# 08_JTAG_DEBUG.net
KiCad netlist of a schematic drawn in Altium Designer
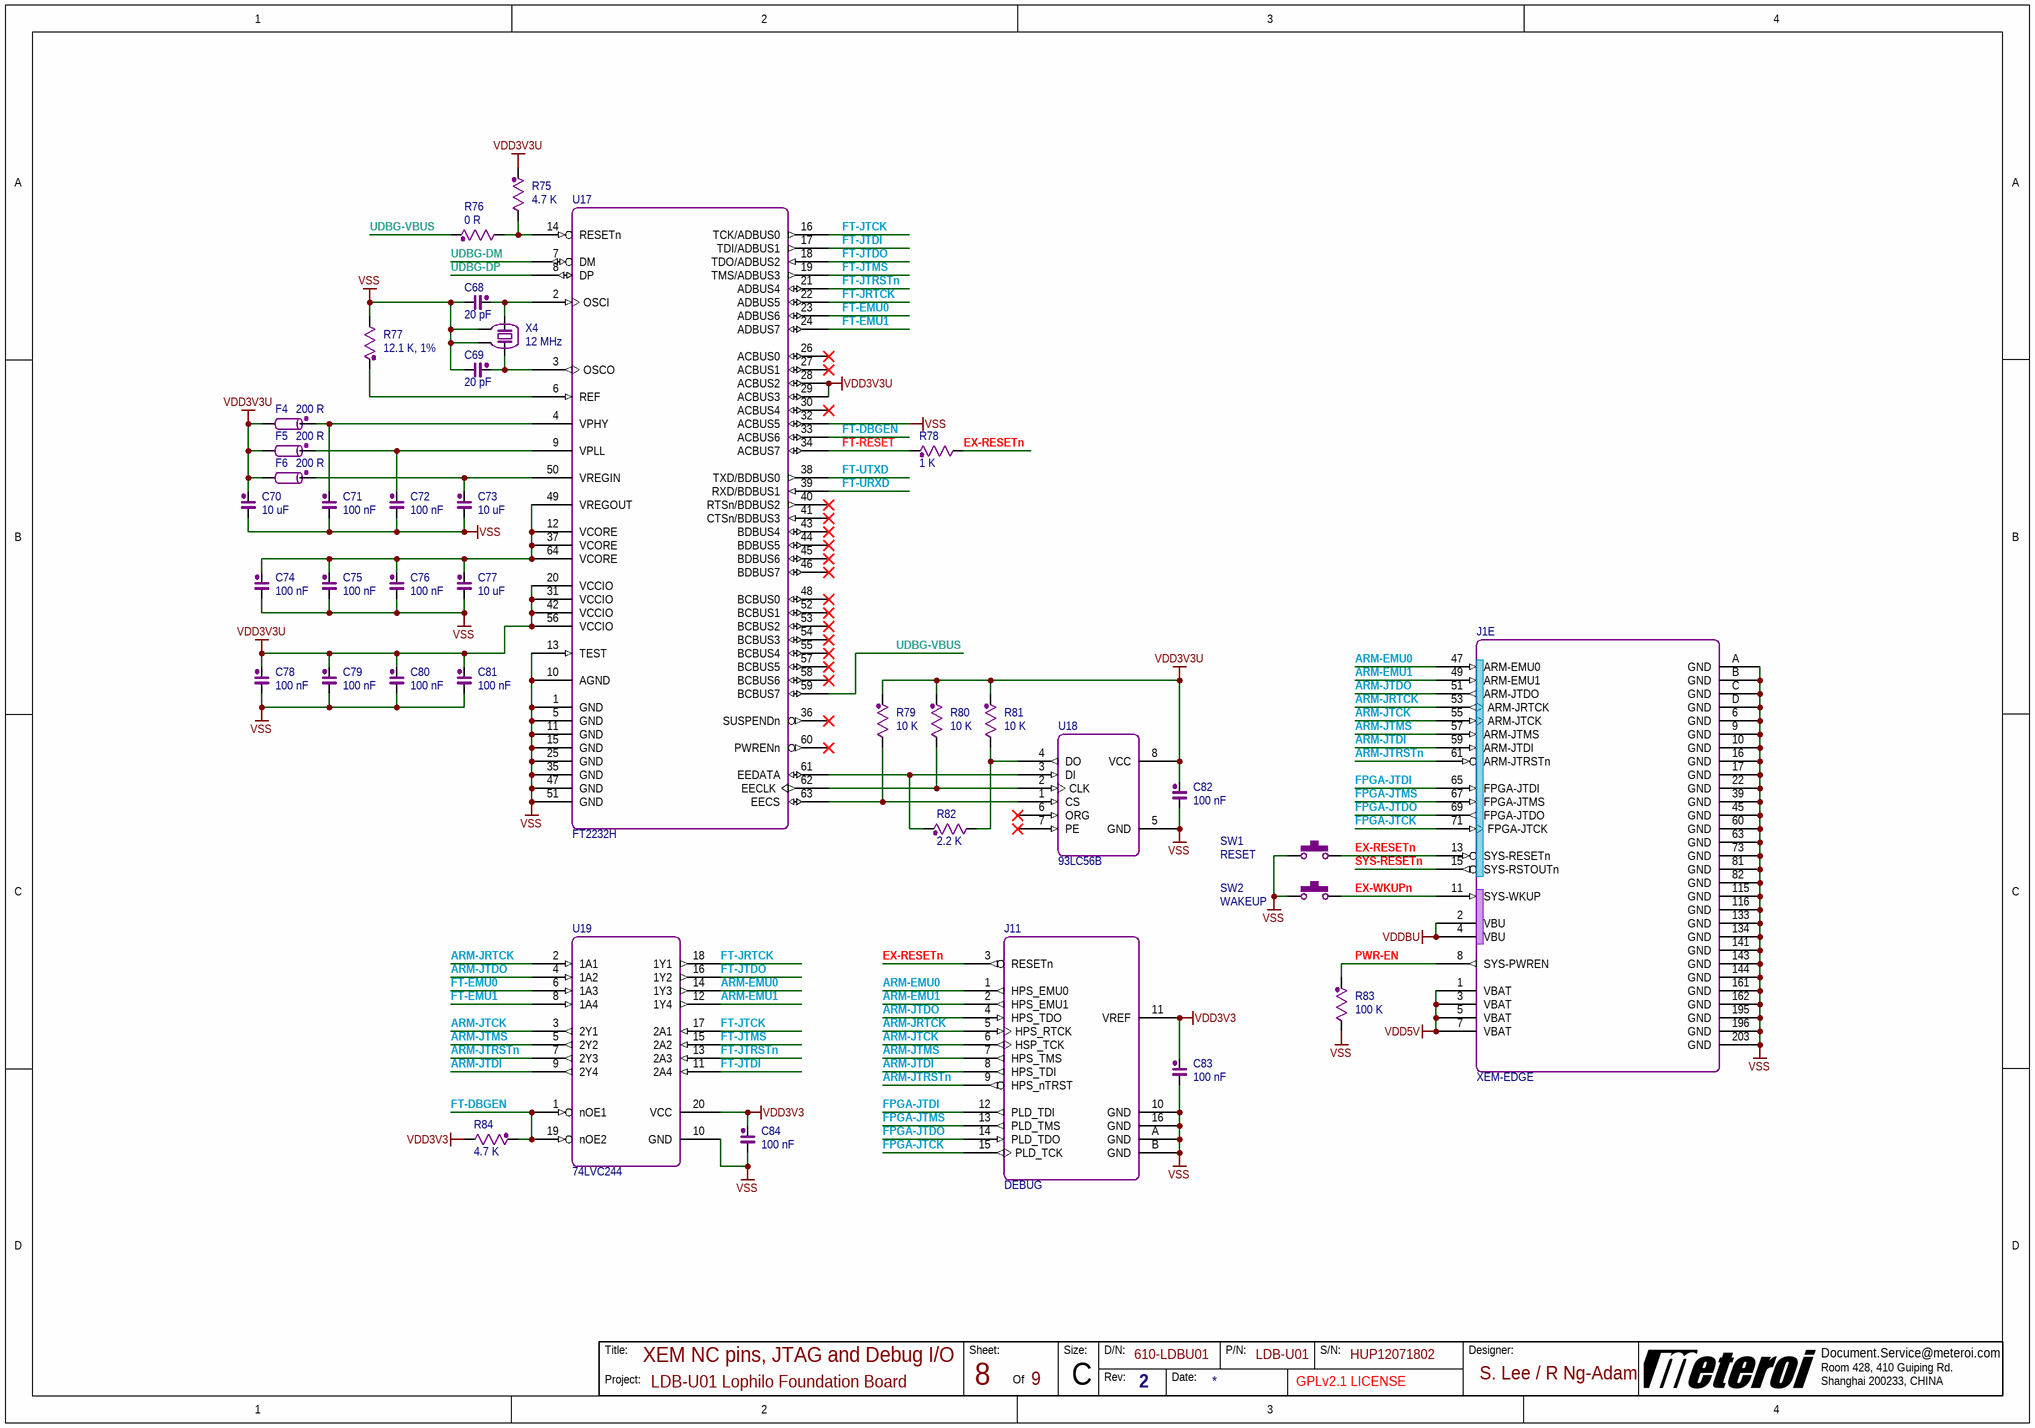
[diagram p0: 08_JTAG_DEBUG.SchDoc]

(export (version "E")
  (design (tool "Eeschema 10.0.6"))
  (components
    (comp (ref "C68")
      (value "20 pF")
      (footprint "0402A1")
      (description "Normal Capacitor")
      (fields
        (field (name "PARTNUMBER") "0")
        (field (name "PUBLISHER") "Cowin")
        (field (name "DESIGNER") "shyul")
      )
      (libsource (lib "") (part "CAP_1"))
    )
    (comp (ref "C69")
      (value "20 pF")
      (footprint "0402A1")
      (description "Normal Capacitor")
      (fields
        (field (name "PARTNUMBER") "0")
        (field (name "PUBLISHER") "Cowin")
        (field (name "DESIGNER") "shyul")
      )
      (libsource (lib "") (part "CAP_1"))
    )
    (comp (ref "C70")
      (value "10 uF")
      (footprint "0603A1")
      (description "Normal Capacitor")
      (fields
        (field (name "PARTNUMBER") "0")
        (field (name "PUBLISHER") "Cowin")
        (field (name "DESIGNER") "shyul")
      )
      (libsource (lib "Basc_1_Passive") (part "CAP"))
    )
    (comp (ref "C71")
      (value "100 nF")
      (footprint "0402A1")
      (description "Normal Capacitor")
      (fields
        (field (name "PARTNUMBER") "0")
        (field (name "PUBLISHER") "Cowin")
        (field (name "DESIGNER") "shyul")
      )
      (libsource (lib "Basc_1_Passive") (part "CAP"))
    )
    (comp (ref "C72")
      (value "100 nF")
      (footprint "0402A1")
      (description "Normal Capacitor")
      (fields
        (field (name "PARTNUMBER") "0")
        (field (name "PUBLISHER") "Cowin")
        (field (name "DESIGNER") "shyul")
      )
      (libsource (lib "Basc_1_Passive") (part "CAP"))
    )
    (comp (ref "C73")
      (value "10 uF")
      (footprint "0603A1")
      (description "Normal Capacitor")
      (fields
        (field (name "PARTNUMBER") "0")
        (field (name "PUBLISHER") "Cowin")
        (field (name "DESIGNER") "shyul")
      )
      (libsource (lib "Basc_1_Passive") (part "CAP"))
    )
    (comp (ref "C74")
      (value "100 nF")
      (footprint "0402A1")
      (description "Normal Capacitor")
      (fields
        (field (name "PARTNUMBER") "0")
        (field (name "PUBLISHER") "Cowin")
        (field (name "DESIGNER") "shyul")
      )
      (libsource (lib "Basc_1_Passive") (part "CAP"))
    )
    (comp (ref "C75")
      (value "100 nF")
      (footprint "0402A1")
      (description "Normal Capacitor")
      (fields
        (field (name "PARTNUMBER") "0")
        (field (name "PUBLISHER") "Cowin")
        (field (name "DESIGNER") "shyul")
      )
      (libsource (lib "Basc_1_Passive") (part "CAP"))
    )
    (comp (ref "C76")
      (value "100 nF")
      (footprint "0402A1")
      (description "Normal Capacitor")
      (fields
        (field (name "PARTNUMBER") "0")
        (field (name "PUBLISHER") "Cowin")
        (field (name "DESIGNER") "shyul")
      )
      (libsource (lib "Basc_1_Passive") (part "CAP"))
    )
    (comp (ref "C77")
      (value "10 uF")
      (footprint "0603A1")
      (description "Normal Capacitor")
      (fields
        (field (name "PARTNUMBER") "0")
        (field (name "PUBLISHER") "Cowin")
        (field (name "DESIGNER") "shyul")
      )
      (libsource (lib "Basc_1_Passive") (part "CAP"))
    )
    (comp (ref "C78")
      (value "100 nF")
      (footprint "0402A1")
      (description "Normal Capacitor")
      (fields
        (field (name "PARTNUMBER") "0")
        (field (name "PUBLISHER") "Cowin")
        (field (name "DESIGNER") "shyul")
      )
      (libsource (lib "Basc_1_Passive") (part "CAP"))
    )
    (comp (ref "C79")
      (value "100 nF")
      (footprint "0402A1")
      (description "Normal Capacitor")
      (fields
        (field (name "PARTNUMBER") "0")
        (field (name "PUBLISHER") "Cowin")
        (field (name "DESIGNER") "shyul")
      )
      (libsource (lib "Basc_1_Passive") (part "CAP"))
    )
    (comp (ref "C80")
      (value "100 nF")
      (footprint "0402A1")
      (description "Normal Capacitor")
      (fields
        (field (name "PARTNUMBER") "0")
        (field (name "PUBLISHER") "Cowin")
        (field (name "DESIGNER") "shyul")
      )
      (libsource (lib "Basc_1_Passive") (part "CAP"))
    )
    (comp (ref "C81")
      (value "100 nF")
      (footprint "0402A1")
      (description "Normal Capacitor")
      (fields
        (field (name "PARTNUMBER") "0")
        (field (name "PUBLISHER") "Cowin")
        (field (name "DESIGNER") "shyul")
      )
      (libsource (lib "Basc_1_Passive") (part "CAP"))
    )
    (comp (ref "C82")
      (value "100 nF")
      (footprint "0402A1")
      (description "Normal Capacitor")
      (fields
        (field (name "PARTNUMBER") "0")
        (field (name "PUBLISHER") "Cowin")
        (field (name "DESIGNER") "shyul")
      )
      (libsource (lib "Basc_1_Passive") (part "CAP"))
    )
    (comp (ref "C83")
      (value "100 nF")
      (footprint "0603A1")
      (description "Normal Capacitor")
      (fields
        (field (name "PARTNUMBER") "0")
        (field (name "PUBLISHER") "Cowin")
        (field (name "DESIGNER") "shyul")
      )
      (libsource (lib "Basc_1_Passive") (part "CAP"))
    )
    (comp (ref "C84")
      (value "100 nF")
      (footprint "0402A1")
      (description "Normal Capacitor")
      (fields
        (field (name "PARTNUMBER") "0")
        (field (name "PUBLISHER") "Cowin")
        (field (name "DESIGNER") "shyul")
      )
      (libsource (lib "Basc_1_Passive") (part "CAP"))
    )
    (comp (ref "F4")
      (value "200 R")
      (footprint "0603A3")
      (description "EMI Bead")
      (fields
        (field (name "PARTNUMBER") "BLM")
        (field (name "DESIGNER") "shyul")
        (field (name "PUBLISHER") "Cowin")
      )
      (libsource (lib "Basc_2_EMI_Protection") (part "BEAD"))
    )
    (comp (ref "F5")
      (value "200 R")
      (footprint "0603A3")
      (description "EMI Bead")
      (fields
        (field (name "PARTNUMBER") "BLM")
        (field (name "DESIGNER") "shyul")
        (field (name "PUBLISHER") "Cowin")
      )
      (libsource (lib "Basc_2_EMI_Protection") (part "BEAD"))
    )
    (comp (ref "F6")
      (value "200 R")
      (footprint "0603A3")
      (description "EMI Bead")
      (fields
        (field (name "PARTNUMBER") "BLM")
        (field (name "DESIGNER") "shyul")
        (field (name "PUBLISHER") "Cowin")
      )
      (libsource (lib "Basc_2_EMI_Protection") (part "BEAD"))
    )
    (comp (ref "J1")
      (value "XEM-EDGE")
      (footprint "XEM-1S-204")
      (description "XEM Edge Connector 204-pins")
      (fields (field (name "PUBLISHER") "Cowin") (field (name "DESIGNER") "shyul"))
      (libsource (lib "PCB_LDB-U01") (part "XEM-SLOT"))
    )
    (comp (ref "J11")
      (value "DEBUG")
      (footprint "HPI_1P25_RA16S")
      (description "JTAG HPI Header")
      (fields (field (name "DESIGNER") "shyul") (field (name "PUBLISHER") "Cowin"))
      (libsource (lib "PCB_MDB-U01") (part "LOP_DEBUG"))
    )
    (comp (ref "R75")
      (value "4.7 K")
      (footprint "0402A2")
      (description "Normal Resistor")
      (fields
        (field (name "PARTNUMBER") "0")
        (field (name "DESIGNER") "shyul")
        (field (name "PUBLISHER") "Cowin")
      )
      (libsource (lib "Basc_1_Passive") (part "RES"))
    )
    (comp (ref "R76")
      (value "0 R")
      (footprint "0402A2")
      (description "Normal Resistor")
      (fields
        (field (name "PARTNUMBER") "0")
        (field (name "DESIGNER") "shyul")
        (field (name "PUBLISHER") "Cowin")
      )
      (libsource (lib "Basc_1_Passive") (part "RES"))
    )
    (comp (ref "R77")
      (value "12.1 K, 1%")
      (footprint "0402A2")
      (description "Normal Resistor")
      (fields
        (field (name "PARTNUMBER") "0")
        (field (name "DESIGNER") "shyul")
        (field (name "PUBLISHER") "Cowin")
      )
      (libsource (lib "Basc_1_Passive") (part "RES"))
    )
    (comp (ref "R78")
      (value "1 K")
      (footprint "0603A2")
      (description "Normal Resistor")
      (fields
        (field (name "PARTNUMBER") "0")
        (field (name "DESIGNER") "shyul")
        (field (name "PUBLISHER") "Cowin")
      )
      (libsource (lib "Basc_1_Passive") (part "RES"))
    )
    (comp (ref "R79")
      (value "10 K")
      (footprint "0402A2")
      (description "Normal Resistor")
      (fields
        (field (name "PARTNUMBER") "0")
        (field (name "DESIGNER") "shyul")
        (field (name "PUBLISHER") "Cowin")
      )
      (libsource (lib "Basc_1_Passive") (part "RES"))
    )
    (comp (ref "R80")
      (value "10 K")
      (footprint "0402A2")
      (description "Normal Resistor")
      (fields
        (field (name "PARTNUMBER") "0")
        (field (name "DESIGNER") "shyul")
        (field (name "PUBLISHER") "Cowin")
      )
      (libsource (lib "Basc_1_Passive") (part "RES"))
    )
    (comp (ref "R81")
      (value "10 K")
      (footprint "0402A2")
      (description "Normal Resistor")
      (fields
        (field (name "PARTNUMBER") "0")
        (field (name "DESIGNER") "shyul")
        (field (name "PUBLISHER") "Cowin")
      )
      (libsource (lib "Basc_1_Passive") (part "RES"))
    )
    (comp (ref "R82")
      (value "2.2 K")
      (footprint "0402A2")
      (description "Normal Resistor")
      (fields
        (field (name "PARTNUMBER") "0")
        (field (name "DESIGNER") "shyul")
        (field (name "PUBLISHER") "Cowin")
      )
      (libsource (lib "Basc_1_Passive") (part "RES"))
    )
    (comp (ref "R83")
      (value "100 K")
      (footprint "0402A2")
      (description "Normal Resistor")
      (fields
        (field (name "PARTNUMBER") "0")
        (field (name "DESIGNER") "shyul")
        (field (name "PUBLISHER") "Cowin")
      )
      (libsource (lib "Basc_1_Passive") (part "RES"))
    )
    (comp (ref "R84")
      (value "4.7 K")
      (footprint "0402A2")
      (description "Normal Resistor")
      (fields
        (field (name "PARTNUMBER") "0")
        (field (name "DESIGNER") "shyul")
        (field (name "PUBLISHER") "Cowin")
      )
      (libsource (lib "Basc_1_Passive") (part "RES"))
    )
    (comp (ref "SW1")
      (value "RESET")
      (footprint "SW_TACT_P_06X06")
      (description "Tactile Switch")
      (fields
        (field (name "PARTNUMBER") "B3F")
        (field (name "DESIGNER") "shyul")
        (field (name "PUBLISHER") "Cowin")
      )
      (libsource (lib "Connector_4_Switch") (part "SW_TACT_A"))
    )
    (comp (ref "SW2")
      (value "WAKEUP")
      (footprint "SW_TACT_P_06X06")
      (description "Tactile Switch")
      (fields
        (field (name "PARTNUMBER") "B3F")
        (field (name "DESIGNER") "shyul")
        (field (name "PUBLISHER") "Cowin")
      )
      (libsource (lib "Connector_4_Switch") (part "SW_TACT_A"))
    )
    (comp (ref "U17")
      (value "FT2232H")
      (footprint "TQFP-64A")
      (description "USB to JTAG/UART")
      (fields
        (field (name "PARTNUMBER") "FT2232HL")
        (field (name "PUBLISHER") "Cowin")
        (field (name "DESIGNER") "shyul")
      )
      (libsource (lib "PCB_MDB-U01") (part "FT2232H"))
    )
    (comp (ref "U18")
      (value "93LC56B")
      (footprint "SOIC-8S")
      (description "Generic Micro Wire ROM")
      (fields
        (field (name "PARTNUMBER") "93LC56BISN")
        (field (name "PUBLISHER") "Cowin")
        (field (name "DESIGNER") "shyul")
      )
      (libsource (lib "IC_03_MCU") (part "ROM_MWIRE"))
    )
    (comp (ref "U19")
      (value "74LVC244")
      (footprint "TSSOP-20")
      (description "8-Bit Driver")
      (fields
        (field (name "PARTNUMBER") "SN74LVC244APW")
        (field (name "DESIGNER") "shyul")
        (field (name "PUBLISHER") "Cowin")
      )
      (libsource (lib "IC_01_Logic") (part "74_244"))
    )
    (comp (ref "X4")
      (value "12 MHz")
      (footprint "OSC_4A_S_3225")
      (description "Crystal")
      (fields
        (field (name "PARTNUMBER") "0")
        (field (name "PUBLISHER") "Cowin")
        (field (name "DESIGNER") "shyul")
      )
      (libsource (lib "Basc_4_Other") (part "OSC_2B"))
    )
  )
  (nets
    (net (code "1") (name "/ARM-EMU0") (class "Default")
      (node (ref "J1") (pin "47") (pinfunction "ARM-EMU0_47") (pintype "input"))
      (node (ref "J11") (pin "1") (pinfunction "HPS_EMU0_1") (pintype "output"))
      (node (ref "U19") (pin "14") (pinfunction "1Y3_14") (pintype "output"))
    )
    (net (code "2") (name "/ARM-EMU1") (class "Default")
      (node (ref "J1") (pin "49") (pinfunction "ARM-EMU1_49") (pintype "input"))
      (node (ref "J11") (pin "2") (pinfunction "HPS_EMU1_2") (pintype "output"))
      (node (ref "U19") (pin "12") (pinfunction "1Y4_12") (pintype "output"))
    )
    (net (code "3") (name "/ARM-JRTCK") (class "Default")
      (node (ref "J1") (pin "53") (pinfunction "ARM-JRTCK_53") (pintype "output"))
      (node (ref "J11") (pin "5") (pinfunction "HPS_RTCK_5") (pintype "input"))
      (node (ref "U19") (pin "2") (pinfunction "1A1_2") (pintype "input"))
    )
    (net (code "4") (name "/ARM-JTCK") (class "Default")
      (node (ref "J1") (pin "55") (pinfunction "ARM-JTCK_55") (pintype "input"))
      (node (ref "J11") (pin "6") (pinfunction "HSP_TCK_6") (pintype "output"))
      (node (ref "U19") (pin "3") (pinfunction "2Y1_3") (pintype "output"))
    )
    (net (code "5") (name "/ARM-JTDI") (class "Default")
      (node (ref "J1") (pin "59") (pinfunction "ARM-JTDI_59") (pintype "input"))
      (node (ref "J11") (pin "8") (pinfunction "HPS_TDI_8") (pintype "output"))
      (node (ref "U19") (pin "9") (pinfunction "2Y4_9") (pintype "output"))
    )
    (net (code "6") (name "/ARM-JTDO") (class "Default")
      (node (ref "J1") (pin "51") (pinfunction "ARM-JTDO_51") (pintype "output"))
      (node (ref "J11") (pin "4") (pinfunction "HPS_TDO_4") (pintype "input"))
      (node (ref "U19") (pin "4") (pinfunction "1A2_4") (pintype "input"))
    )
    (net (code "7") (name "/ARM-JTMS") (class "Default")
      (node (ref "J1") (pin "57") (pinfunction "ARM-JTMS_57") (pintype "input"))
      (node (ref "J11") (pin "7") (pinfunction "HPS_TMS_7") (pintype "output"))
      (node (ref "U19") (pin "5") (pinfunction "2Y2_5") (pintype "output"))
    )
    (net (code "8") (name "/ARM-JTRSTn") (class "Default")
      (node (ref "J1") (pin "61") (pinfunction "ARM-JTRSTn_61") (pintype "input"))
      (node (ref "J11") (pin "9") (pinfunction "HPS_nTRST_9") (pintype "output"))
      (node (ref "U19") (pin "7") (pinfunction "2Y3_7") (pintype "output"))
    )
    (net (code "9") (name "/EX-RESETn") (class "Default")
      (node (ref "J1") (pin "13") (pinfunction "SYS-RESETn_13") (pintype "input"))
      (node (ref "J11") (pin "3") (pinfunction "RESETn_3") (pintype "output"))
      (node (ref "R78") (pin "1") (pinfunction "1_1") (pintype "passive"))
      (node (ref "SW1") (pin "2") (pinfunction "KB_2") (pintype "passive"))
    )
    (net (code "10") (name "/EX-WKUPn") (class "Default")
      (node (ref "J1") (pin "11") (pinfunction "SYS-WKUP_11") (pintype "input"))
      (node (ref "SW2") (pin "2") (pinfunction "KB_2") (pintype "passive"))
    )
    (net (code "11") (name "/FPGA-JTCK") (class "Default")
      (node (ref "J1") (pin "71") (pinfunction "FPGA-JTCK_71") (pintype "input"))
      (node (ref "J11") (pin "15") (pinfunction "PLD_TCK_15") (pintype "output"))
    )
    (net (code "12") (name "/FPGA-JTDI") (class "Default")
      (node (ref "J1") (pin "65") (pinfunction "FPGA-JTDI_65") (pintype "input"))
      (node (ref "J11") (pin "12") (pinfunction "PLD_TDI_12") (pintype "output"))
    )
    (net (code "13") (name "/FPGA-JTDO") (class "Default")
      (node (ref "J1") (pin "69") (pinfunction "FPGA-JTDO_69") (pintype "output"))
      (node (ref "J11") (pin "14") (pinfunction "PLD_TDO_14") (pintype "input"))
    )
    (net (code "14") (name "/FPGA-JTMS") (class "Default")
      (node (ref "J1") (pin "67") (pinfunction "FPGA-JTMS_67") (pintype "input"))
      (node (ref "J11") (pin "13") (pinfunction "PLD_TMS_13") (pintype "output"))
    )
    (net (code "15") (name "/FT-DBGEN") (class "Default")
      (node (ref "R84") (pin "2") (pinfunction "2_2") (pintype "passive"))
      (node (ref "U17") (pin "33") (pinfunction "ACBUS6_33") (pintype "bidirectional"))
      (node (ref "U19") (pin "1") (pinfunction "nOE1_1") (pintype "input"))
      (node (ref "U19") (pin "19") (pinfunction "nOE2_19") (pintype "input"))
    )
    (net (code "16") (name "/FT-EMU0") (class "Default")
      (node (ref "U17") (pin "23") (pinfunction "ADBUS6_23") (pintype "bidirectional"))
      (node (ref "U19") (pin "6") (pinfunction "1A3_6") (pintype "input"))
    )
    (net (code "17") (name "/FT-EMU1") (class "Default")
      (node (ref "U17") (pin "24") (pinfunction "ADBUS7_24") (pintype "bidirectional"))
      (node (ref "U19") (pin "8") (pinfunction "1A4_8") (pintype "input"))
    )
    (net (code "18") (name "/FT-JRTCK") (class "Default")
      (node (ref "U17") (pin "22") (pinfunction "ADBUS5_22") (pintype "bidirectional"))
      (node (ref "U19") (pin "18") (pinfunction "1Y1_18") (pintype "output"))
    )
    (net (code "19") (name "/FT-JTCK") (class "Default")
      (node (ref "U17") (pin "16") (pinfunction "TCK/ADBUS0_16") (pintype "output"))
      (node (ref "U19") (pin "17") (pinfunction "2A1_17") (pintype "input"))
    )
    (net (code "20") (name "/FT-JTDI") (class "Default")
      (node (ref "U17") (pin "17") (pinfunction "TDI/ADBUS1_17") (pintype "output"))
      (node (ref "U19") (pin "11") (pinfunction "2A4_11") (pintype "input"))
    )
    (net (code "21") (name "/FT-JTDO") (class "Default")
      (node (ref "U17") (pin "18") (pinfunction "TDO/ADBUS2_18") (pintype "input"))
      (node (ref "U19") (pin "16") (pinfunction "1Y2_16") (pintype "output"))
    )
    (net (code "22") (name "/FT-JTMS") (class "Default")
      (node (ref "U17") (pin "19") (pinfunction "TMS/ADBUS3_19") (pintype "output"))
      (node (ref "U19") (pin "15") (pinfunction "2A2_15") (pintype "input"))
    )
    (net (code "23") (name "/FT-JTRSTn") (class "Default")
      (node (ref "U17") (pin "21") (pinfunction "ADBUS4_21") (pintype "bidirectional"))
      (node (ref "U19") (pin "13") (pinfunction "2A3_13") (pintype "input"))
    )
    (net (code "24") (name "/FT-RESET") (class "Default")
      (node (ref "R78") (pin "2") (pinfunction "2_2") (pintype "passive"))
      (node (ref "U17") (pin "34") (pinfunction "ACBUS7_34") (pintype "bidirectional"))
    )
    (net (code "25") (name "/FT-URXD") (class "Default")
      (node (ref "U17") (pin "39") (pinfunction "RXD/BDBUS1_39") (pintype "input"))
    )
    (net (code "26") (name "/FT-UTXD") (class "Default")
      (node (ref "U17") (pin "38") (pinfunction "TXD/BDBUS0_38") (pintype "output"))
    )
    (net (code "27") (name "/PWR-EN") (class "Default")
      (node (ref "J1") (pin "8") (pinfunction "SYS-PWREN_8") (pintype "output"))
      (node (ref "R83") (pin "2") (pinfunction "2_2") (pintype "passive"))
    )
    (net (code "28") (name "/SYS-RESETn") (class "Default")
      (node (ref "J1") (pin "15") (pinfunction "SYS-RSTOUTn_15") (pintype "output"))
    )
    (net (code "29") (name "/UDBG-DM") (class "Default")
      (node (ref "U17") (pin "7") (pinfunction "DM_7") (pintype "bidirectional"))
    )
    (net (code "30") (name "/UDBG-DP") (class "Default")
      (node (ref "U17") (pin "8") (pinfunction "DP_8") (pintype "bidirectional"))
    )
    (net (code "31") (name "/UDBG-VBUS") (class "Default")
      (node (ref "R76") (pin "2") (pinfunction "2_2") (pintype "passive"))
      (node (ref "U17") (pin "59") (pinfunction "BCBUS7_59") (pintype "bidirectional"))
    )
    (net (code "32") (name "Net-(U17-EECLK)") (class "Default")
      (node (ref "R80") (pin "1") (pinfunction "1_1") (pintype "passive"))
      (node (ref "U17") (pin "62") (pinfunction "EECLK_62") (pintype "output"))
      (node (ref "U18") (pin "2") (pinfunction "CLK_2") (pintype "input"))
    )
    (net (code "33") (name "Net-(U17-EECS)") (class "Default")
      (node (ref "R79") (pin "1") (pinfunction "1_1") (pintype "passive"))
      (node (ref "U17") (pin "63") (pinfunction "EECS_63") (pintype "bidirectional"))
      (node (ref "U18") (pin "1") (pinfunction "CS_1") (pintype "input"))
    )
    (net (code "34") (name "Net-(U17-EEDATA)") (class "Default")
      (node (ref "R82") (pin "2") (pinfunction "2_2") (pintype "passive"))
      (node (ref "U17") (pin "61") (pinfunction "EEDATA_61") (pintype "bidirectional"))
      (node (ref "U18") (pin "3") (pinfunction "DI_3") (pintype "input"))
    )
    (net (code "35") (name "Net-(U17-OSCI)") (class "Default")
      (node (ref "C68") (pin "2") (pinfunction "2_2") (pintype "passive"))
      (node (ref "U17") (pin "2") (pinfunction "OSCI_2") (pintype "input"))
      (node (ref "X4") (pin "1") (pinfunction "1_1") (pintype "passive"))
    )
    (net (code "36") (name "Net-(U17-OSCO)") (class "Default")
      (node (ref "C69") (pin "2") (pinfunction "2_2") (pintype "passive"))
      (node (ref "U17") (pin "3") (pinfunction "OSCO_3") (pintype "output"))
      (node (ref "X4") (pin "3") (pinfunction "3_3") (pintype "passive"))
    )
    (net (code "37") (name "Net-(U17-REF)") (class "Default")
      (node (ref "R77") (pin "2") (pinfunction "2_2") (pintype "passive"))
      (node (ref "U17") (pin "6") (pinfunction "REF_6") (pintype "input"))
    )
    (net (code "38") (name "Net-(U17-RESETn)") (class "Default")
      (node (ref "R75") (pin "1") (pinfunction "1_1") (pintype "passive"))
      (node (ref "R76") (pin "1") (pinfunction "1_1") (pintype "passive"))
      (node (ref "U17") (pin "14") (pinfunction "RESETn_14") (pintype "input"))
    )
    (net (code "39") (name "Net-(U17-VPHY)") (class "Default")
      (node (ref "C71") (pin "2") (pinfunction "2_2") (pintype "passive"))
      (node (ref "F4") (pin "2") (pinfunction "2_2") (pintype "passive"))
      (node (ref "U17") (pin "4") (pinfunction "VPHY_4") (pintype "passive"))
    )
    (net (code "40") (name "Net-(U17-VPLL)") (class "Default")
      (node (ref "C72") (pin "2") (pinfunction "2_2") (pintype "passive"))
      (node (ref "F5") (pin "2") (pinfunction "2_2") (pintype "passive"))
      (node (ref "U17") (pin "9") (pinfunction "VPLL_9") (pintype "passive"))
    )
    (net (code "41") (name "Net-(U17-VREGIN)") (class "Default")
      (node (ref "C73") (pin "2") (pinfunction "2_2") (pintype "passive"))
      (node (ref "F6") (pin "2") (pinfunction "2_2") (pintype "passive"))
      (node (ref "U17") (pin "50") (pinfunction "VREGIN_50") (pintype "passive"))
    )
    (net (code "42") (name "Net-(U17-VREGOUT)") (class "Default")
      (node (ref "C74") (pin "2") (pinfunction "2_2") (pintype "passive"))
      (node (ref "C75") (pin "2") (pinfunction "2_2") (pintype "passive"))
      (node (ref "C76") (pin "2") (pinfunction "2_2") (pintype "passive"))
      (node (ref "C77") (pin "2") (pinfunction "2_2") (pintype "passive"))
      (node (ref "U17") (pin "12") (pinfunction "VCORE_12") (pintype "passive"))
      (node (ref "U17") (pin "37") (pinfunction "VCORE_37") (pintype "passive"))
      (node (ref "U17") (pin "49") (pinfunction "VREGOUT_49") (pintype "power_in"))
      (node (ref "U17") (pin "64") (pinfunction "VCORE_64") (pintype "passive"))
    )
    (net (code "43") (name "Net-(U18-DO)") (class "Default")
      (node (ref "R81") (pin "1") (pinfunction "1_1") (pintype "passive"))
      (node (ref "R82") (pin "1") (pinfunction "1_1") (pintype "passive"))
      (node (ref "U18") (pin "4") (pinfunction "DO_4") (pintype "output"))
    )
    (net (code "44") (name "VDD3V3") (class "Default")
      (node (ref "C83") (pin "2") (pinfunction "2_2") (pintype "passive"))
      (node (ref "C84") (pin "2") (pinfunction "2_2") (pintype "passive"))
      (node (ref "J11") (pin "11") (pinfunction "VREF_11") (pintype "passive"))
      (node (ref "R84") (pin "1") (pinfunction "1_1") (pintype "passive"))
      (node (ref "U19") (pin "20") (pinfunction "VCC_20") (pintype "passive"))
    )
    (net (code "45") (name "VDD3V3U") (class "Default")
      (node (ref "C70") (pin "2") (pinfunction "2_2") (pintype "passive"))
      (node (ref "C78") (pin "2") (pinfunction "2_2") (pintype "passive"))
      (node (ref "C79") (pin "2") (pinfunction "2_2") (pintype "passive"))
      (node (ref "C80") (pin "2") (pinfunction "2_2") (pintype "passive"))
      (node (ref "C81") (pin "2") (pinfunction "2_2") (pintype "passive"))
      (node (ref "C82") (pin "2") (pinfunction "2_2") (pintype "passive"))
      (node (ref "F4") (pin "1") (pinfunction "1_1") (pintype "passive"))
      (node (ref "F5") (pin "1") (pinfunction "1_1") (pintype "passive"))
      (node (ref "F6") (pin "1") (pinfunction "1_1") (pintype "passive"))
      (node (ref "R75") (pin "2") (pinfunction "2_2") (pintype "passive"))
      (node (ref "R79") (pin "2") (pinfunction "2_2") (pintype "passive"))
      (node (ref "R80") (pin "2") (pinfunction "2_2") (pintype "passive"))
      (node (ref "R81") (pin "2") (pinfunction "2_2") (pintype "passive"))
      (node (ref "U17") (pin "20") (pinfunction "VCCIO_20") (pintype "passive"))
      (node (ref "U17") (pin "28") (pinfunction "ACBUS2_28") (pintype "bidirectional"))
      (node (ref "U17") (pin "29") (pinfunction "ACBUS3_29") (pintype "bidirectional"))
      (node (ref "U17") (pin "31") (pinfunction "VCCIO_31") (pintype "passive"))
      (node (ref "U17") (pin "42") (pinfunction "VCCIO_42") (pintype "passive"))
      (node (ref "U17") (pin "56") (pinfunction "VCCIO_56") (pintype "passive"))
      (node (ref "U18") (pin "8") (pinfunction "VCC_8") (pintype "power_in"))
    )
    (net (code "46") (name "VDD5V") (class "Default")
      (node (ref "J1") (pin "1") (pinfunction "VBAT_1") (pintype "passive"))
      (node (ref "J1") (pin "3") (pinfunction "VBAT_3") (pintype "passive"))
      (node (ref "J1") (pin "5") (pinfunction "VBAT_5") (pintype "passive"))
      (node (ref "J1") (pin "7") (pinfunction "VBAT_7") (pintype "passive"))
    )
    (net (code "47") (name "VDDBU") (class "Default")
      (node (ref "J1") (pin "2") (pinfunction "VBU_2") (pintype "passive"))
      (node (ref "J1") (pin "4") (pinfunction "VBU_4") (pintype "passive"))
    )
    (net (code "48") (name "VSS") (class "Default")
      (node (ref "C68") (pin "1") (pinfunction "1_1") (pintype "passive"))
      (node (ref "C69") (pin "1") (pinfunction "1_1") (pintype "passive"))
      (node (ref "C70") (pin "1") (pinfunction "1_1") (pintype "passive"))
      (node (ref "C71") (pin "1") (pinfunction "1_1") (pintype "passive"))
      (node (ref "C72") (pin "1") (pinfunction "1_1") (pintype "passive"))
      (node (ref "C73") (pin "1") (pinfunction "1_1") (pintype "passive"))
      (node (ref "C74") (pin "1") (pinfunction "1_1") (pintype "passive"))
      (node (ref "C75") (pin "1") (pinfunction "1_1") (pintype "passive"))
      (node (ref "C76") (pin "1") (pinfunction "1_1") (pintype "passive"))
      (node (ref "C77") (pin "1") (pinfunction "1_1") (pintype "passive"))
      (node (ref "C78") (pin "1") (pinfunction "1_1") (pintype "passive"))
      (node (ref "C79") (pin "1") (pinfunction "1_1") (pintype "passive"))
      (node (ref "C80") (pin "1") (pinfunction "1_1") (pintype "passive"))
      (node (ref "C81") (pin "1") (pinfunction "1_1") (pintype "passive"))
      (node (ref "C82") (pin "1") (pinfunction "1_1") (pintype "passive"))
      (node (ref "C83") (pin "1") (pinfunction "1_1") (pintype "passive"))
      (node (ref "C84") (pin "1") (pinfunction "1_1") (pintype "passive"))
      (node (ref "J1") (pin "10") (pinfunction "GND_10") (pintype "passive"))
      (node (ref "J1") (pin "115") (pinfunction "GND_115") (pintype "passive"))
      (node (ref "J1") (pin "116") (pinfunction "GND_116") (pintype "passive"))
      (node (ref "J1") (pin "133") (pinfunction "GND_133") (pintype "passive"))
      (node (ref "J1") (pin "134") (pinfunction "GND_134") (pintype "passive"))
      (node (ref "J1") (pin "141") (pinfunction "GND_141") (pintype "passive"))
      (node (ref "J1") (pin "143") (pinfunction "GND_143") (pintype "passive"))
      (node (ref "J1") (pin "144") (pinfunction "GND_144") (pintype "passive"))
      (node (ref "J1") (pin "16") (pinfunction "GND_16") (pintype "passive"))
      (node (ref "J1") (pin "161") (pinfunction "GND_161") (pintype "passive"))
      (node (ref "J1") (pin "162") (pinfunction "GND_162") (pintype "passive"))
      (node (ref "J1") (pin "17") (pinfunction "GND_17") (pintype "passive"))
      (node (ref "J1") (pin "195") (pinfunction "GND_195") (pintype "passive"))
      (node (ref "J1") (pin "196") (pinfunction "GND_196") (pintype "passive"))
      (node (ref "J1") (pin "203") (pinfunction "GND_203") (pintype "passive"))
      (node (ref "J1") (pin "22") (pinfunction "GND_22") (pintype "passive"))
      (node (ref "J1") (pin "39") (pinfunction "GND_39") (pintype "passive"))
      (node (ref "J1") (pin "45") (pinfunction "GND_45") (pintype "passive"))
      (node (ref "J1") (pin "6") (pinfunction "GND_6") (pintype "passive"))
      (node (ref "J1") (pin "60") (pinfunction "GND_60") (pintype "passive"))
      (node (ref "J1") (pin "63") (pinfunction "GND_63") (pintype "passive"))
      (node (ref "J1") (pin "73") (pinfunction "GND_73") (pintype "passive"))
      (node (ref "J1") (pin "81") (pinfunction "GND_81") (pintype "passive"))
      (node (ref "J1") (pin "82") (pinfunction "GND_82") (pintype "passive"))
      (node (ref "J1") (pin "9") (pinfunction "GND_9") (pintype "passive"))
      (node (ref "J1") (pin "A") (pinfunction "GND_A") (pintype "passive"))
      (node (ref "J1") (pin "B") (pinfunction "GND_B") (pintype "passive"))
      (node (ref "J1") (pin "C") (pinfunction "GND_C") (pintype "passive"))
      (node (ref "J1") (pin "D") (pinfunction "GND_D") (pintype "passive"))
      (node (ref "J11") (pin "10") (pinfunction "GND_10") (pintype "passive"))
      (node (ref "J11") (pin "16") (pinfunction "GND_16") (pintype "passive"))
      (node (ref "J11") (pin "A") (pinfunction "GND_A") (pintype "power_in"))
      (node (ref "J11") (pin "B") (pinfunction "GND_B") (pintype "power_in"))
      (node (ref "R77") (pin "1") (pinfunction "1_1") (pintype "passive"))
      (node (ref "R83") (pin "1") (pinfunction "1_1") (pintype "passive"))
      (node (ref "SW1") (pin "1") (pinfunction "KA_1") (pintype "passive"))
      (node (ref "SW2") (pin "1") (pinfunction "KA_1") (pintype "passive"))
      (node (ref "U17") (pin "1") (pinfunction "GND_1") (pintype "passive"))
      (node (ref "U17") (pin "10") (pinfunction "AGND_10") (pintype "passive"))
      (node (ref "U17") (pin "11") (pinfunction "GND_11") (pintype "passive"))
      (node (ref "U17") (pin "13") (pinfunction "TEST_13") (pintype "input"))
      (node (ref "U17") (pin "15") (pinfunction "GND_15") (pintype "passive"))
      (node (ref "U17") (pin "25") (pinfunction "GND_25") (pintype "passive"))
      (node (ref "U17") (pin "32") (pinfunction "ACBUS5_32") (pintype "bidirectional"))
      (node (ref "U17") (pin "35") (pinfunction "GND_35") (pintype "passive"))
      (node (ref "U17") (pin "47") (pinfunction "GND_47") (pintype "passive"))
      (node (ref "U17") (pin "5") (pinfunction "GND_5") (pintype "passive"))
      (node (ref "U17") (pin "51") (pinfunction "GND_51") (pintype "passive"))
      (node (ref "U18") (pin "5") (pinfunction "GND_5") (pintype "power_in"))
      (node (ref "U19") (pin "10") (pinfunction "GND_10") (pintype "passive"))
      (node (ref "X4") (pin "2") (pinfunction "2_2") (pintype "passive"))
      (node (ref "X4") (pin "4") (pinfunction "4_4") (pintype "passive"))
    )
    (net (code "49") (name "unconnected-(U17-ACBUS0-Pad26)") (class "Default")
      (node (ref "U17") (pin "26") (pinfunction "ACBUS0_26") (pintype "bidirectional+no_connect"))
    )
    (net (code "50") (name "unconnected-(U17-ACBUS1-Pad27)") (class "Default")
      (node (ref "U17") (pin "27") (pinfunction "ACBUS1_27") (pintype "bidirectional+no_connect"))
    )
    (net (code "51") (name "unconnected-(U17-ACBUS4-Pad30)") (class "Default")
      (node (ref "U17") (pin "30") (pinfunction "ACBUS4_30") (pintype "bidirectional+no_connect"))
    )
    (net (code "52") (name "unconnected-(U17-BCBUS0-Pad48)") (class "Default")
      (node (ref "U17") (pin "48") (pinfunction "BCBUS0_48") (pintype "bidirectional+no_connect"))
    )
    (net (code "53") (name "unconnected-(U17-BCBUS1-Pad52)") (class "Default")
      (node (ref "U17") (pin "52") (pinfunction "BCBUS1_52") (pintype "bidirectional+no_connect"))
    )
    (net (code "54") (name "unconnected-(U17-BCBUS2-Pad53)") (class "Default")
      (node (ref "U17") (pin "53") (pinfunction "BCBUS2_53") (pintype "bidirectional+no_connect"))
    )
    (net (code "55") (name "unconnected-(U17-BCBUS3-Pad54)") (class "Default")
      (node (ref "U17") (pin "54") (pinfunction "BCBUS3_54") (pintype "bidirectional+no_connect"))
    )
    (net (code "56") (name "unconnected-(U17-BCBUS4-Pad55)") (class "Default")
      (node (ref "U17") (pin "55") (pinfunction "BCBUS4_55") (pintype "bidirectional+no_connect"))
    )
    (net (code "57") (name "unconnected-(U17-BCBUS5-Pad57)") (class "Default")
      (node (ref "U17") (pin "57") (pinfunction "BCBUS5_57") (pintype "bidirectional+no_connect"))
    )
    (net (code "58") (name "unconnected-(U17-BCBUS6-Pad58)") (class "Default")
      (node (ref "U17") (pin "58") (pinfunction "BCBUS6_58") (pintype "bidirectional+no_connect"))
    )
    (net (code "59") (name "unconnected-(U17-BDBUS4-Pad43)") (class "Default")
      (node (ref "U17") (pin "43") (pinfunction "BDBUS4_43") (pintype "bidirectional+no_connect"))
    )
    (net (code "60") (name "unconnected-(U17-BDBUS5-Pad44)") (class "Default")
      (node (ref "U17") (pin "44") (pinfunction "BDBUS5_44") (pintype "bidirectional+no_connect"))
    )
    (net (code "61") (name "unconnected-(U17-BDBUS6-Pad45)") (class "Default")
      (node (ref "U17") (pin "45") (pinfunction "BDBUS6_45") (pintype "bidirectional+no_connect"))
    )
    (net (code "62") (name "unconnected-(U17-BDBUS7-Pad46)") (class "Default")
      (node (ref "U17") (pin "46") (pinfunction "BDBUS7_46") (pintype "bidirectional+no_connect"))
    )
    (net (code "63") (name "unconnected-(U17-CTSn{slash}BDBUS3-Pad41)") (class "Default")
      (node (ref "U17") (pin "41") (pinfunction "CTSn/BDBUS3_41") (pintype "input+no_connect"))
    )
    (net (code "64") (name "unconnected-(U17-PWRENn-Pad60)") (class "Default")
      (node (ref "U17") (pin "60") (pinfunction "PWRENn_60") (pintype "output+no_connect"))
    )
    (net (code "65") (name "unconnected-(U17-RTSn{slash}BDBUS2-Pad40)") (class "Default")
      (node (ref "U17") (pin "40") (pinfunction "RTSn/BDBUS2_40") (pintype "output+no_connect"))
    )
    (net (code "66") (name "unconnected-(U17-SUSPENDn-Pad36)") (class "Default")
      (node (ref "U17") (pin "36") (pinfunction "SUSPENDn_36") (pintype "output+no_connect"))
    )
    (net (code "67") (name "unconnected-(U18-ORG-Pad6)") (class "Default")
      (node (ref "U18") (pin "6") (pinfunction "ORG_6") (pintype "input+no_connect"))
    )
    (net (code "68") (name "unconnected-(U18-PE-Pad7)") (class "Default")
      (node (ref "U18") (pin "7") (pinfunction "PE_7") (pintype "input+no_connect"))
    )
  )
)
